# m10motor.net
KiCad netlist of a schematic drawn in Altium Designer
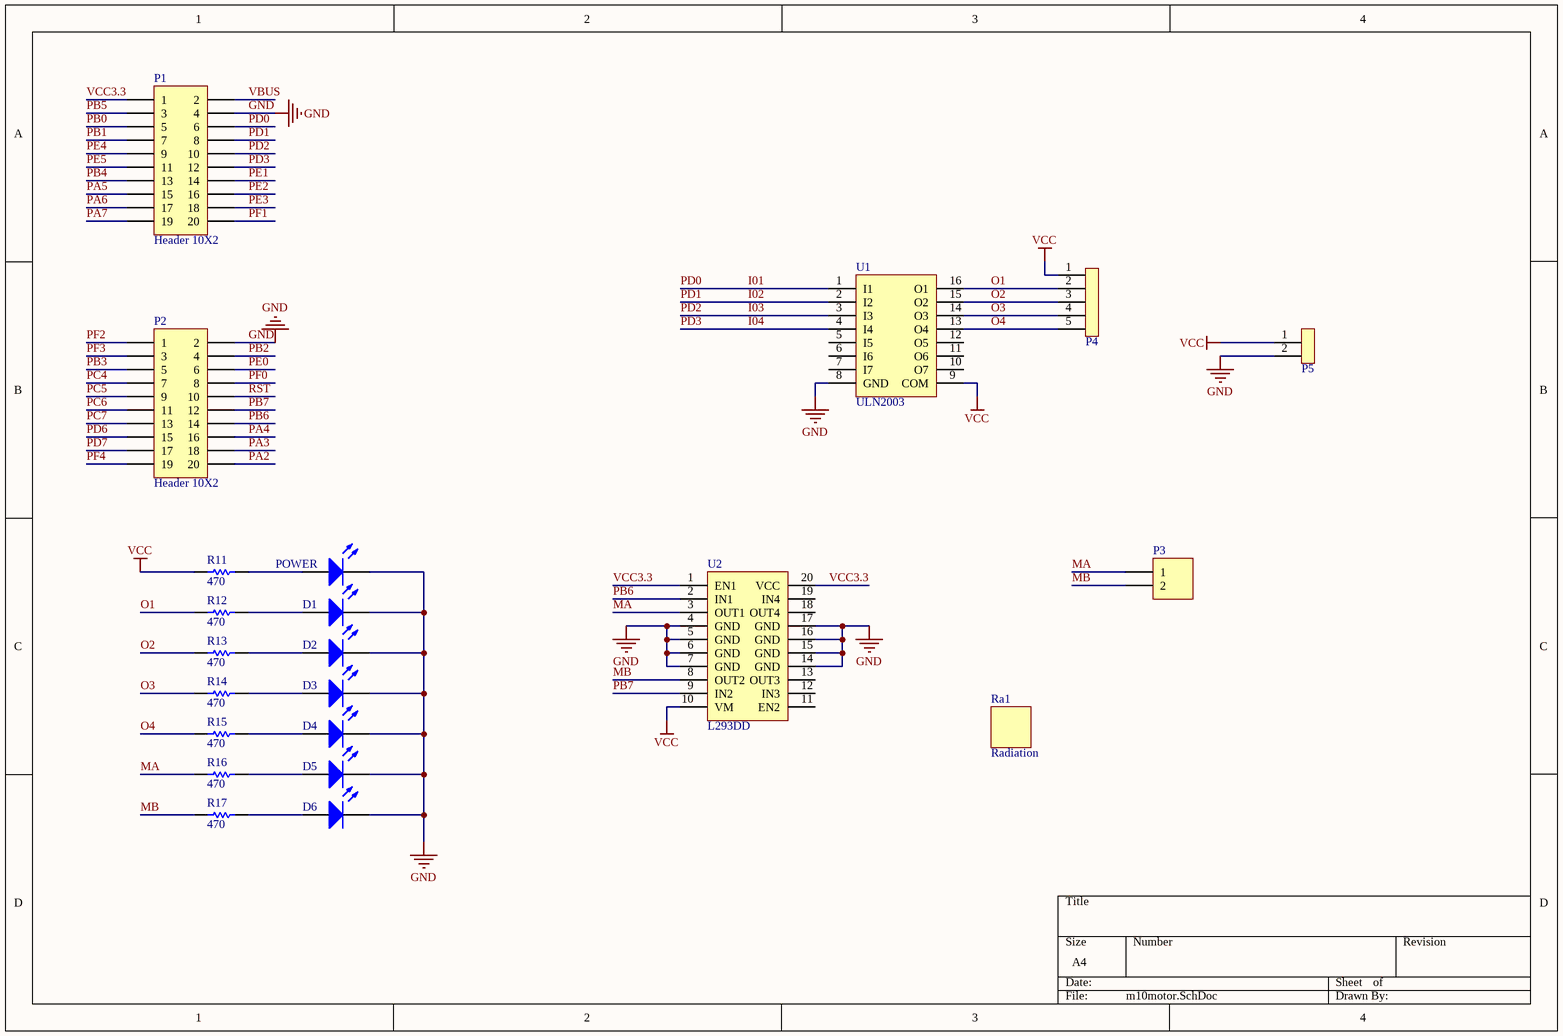
[diagram p0: m10motor.SchDoc]

(export (version "E")
  (design (tool "Eeschema 10.0.6"))
  (components
    (comp (ref "D1")
      (value "LED2")
      (footprint "LED_0603_RED")
      (description "Typical RED, GREEN, YELLOW, AMBER GaAs LED")
      (fields (field (name "PUBLISHER") "Altium Limited"))
      (libsource (lib "Miscellaneous Devices") (part "LED2"))
    )
    (comp (ref "D2")
      (value "LED2")
      (footprint "LED_0603_RED")
      (description "Typical RED, GREEN, YELLOW, AMBER GaAs LED")
      (fields (field (name "PUBLISHER") "Altium Limited"))
      (libsource (lib "Miscellaneous Devices") (part "LED2"))
    )
    (comp (ref "D3")
      (value "LED2")
      (footprint "LED_0603_RED")
      (description "Typical RED, GREEN, YELLOW, AMBER GaAs LED")
      (fields (field (name "PUBLISHER") "Altium Limited"))
      (libsource (lib "Miscellaneous Devices") (part "LED2"))
    )
    (comp (ref "D4")
      (value "LED2")
      (footprint "LED_0603_RED")
      (description "Typical RED, GREEN, YELLOW, AMBER GaAs LED")
      (fields (field (name "PUBLISHER") "Altium Limited"))
      (libsource (lib "Miscellaneous Devices") (part "LED2"))
    )
    (comp (ref "D5")
      (value "LED2")
      (footprint "LED_0603_RED")
      (description "Typical RED, GREEN, YELLOW, AMBER GaAs LED")
      (fields (field (name "PUBLISHER") "Altium Limited"))
      (libsource (lib "Miscellaneous Devices") (part "LED2"))
    )
    (comp (ref "D6")
      (value "LED2")
      (footprint "LED_0603_RED")
      (description "Typical RED, GREEN, YELLOW, AMBER GaAs LED")
      (fields (field (name "PUBLISHER") "Altium Limited"))
      (libsource (lib "Miscellaneous Devices") (part "LED2"))
    )
    (comp (ref "P1")
      (value "Header 10X2")
      (footprint "HDR2X10")
      (description "Header, 10-Pin, Dual row")
      (fields (field (name "PUBLISHER") "Altium Limited"))
      (libsource (lib "Miscellaneous Connectors") (part "Header 10X2"))
    )
    (comp (ref "P2")
      (value "Header 10X2")
      (footprint "HDR2X10")
      (description "Header, 10-Pin, Dual row")
      (fields (field (name "PUBLISHER") "Altium Limited"))
      (libsource (lib "Miscellaneous Connectors") (part "Header 10X2"))
    )
    (comp (ref "P3")
      (value "Header 2")
      (footprint "MKDSN_2RMI")
      (description "Header, 2-Pin")
      (fields (field (name "PUBLISHER") "Altium Limited"))
      (libsource (lib "Miscellaneous Connectors") (part "Header 2"))
    )
    (comp (ref "P4") (value "Header5") (footprint "XHP5") (libsource (lib "m13") (part "Header5")))
    (comp (ref "P5") (value "Header2") (footprint "MKDSN_2RMI") (libsource (lib "m13") (part "Header2")))
    (comp (ref "POWER")
      (value "LED2")
      (footprint "LED_0603_RED")
      (description "Typical RED, GREEN, YELLOW, AMBER GaAs LED")
      (fields (field (name "PUBLISHER") "Altium Limited"))
      (libsource (lib "Miscellaneous Devices") (part "LED2"))
    )
    (comp (ref "R11")
      (value "470")
      (footprint "RES_0603")
      (description "Semiconductor Resistor")
      (fields (field (name "Comment") "Res Semi") (field (name "PUBLISHER") "Altium Limited"))
      (libsource (lib "Miscellaneous Devices") (part "Res Semi"))
    )
    (comp (ref "R12")
      (value "470")
      (footprint "RES_0603")
      (description "Semiconductor Resistor")
      (fields (field (name "Comment") "Res Semi") (field (name "PUBLISHER") "Altium Limited"))
      (libsource (lib "Miscellaneous Devices") (part "Res Semi"))
    )
    (comp (ref "R13")
      (value "470")
      (footprint "RES_0603")
      (description "Semiconductor Resistor")
      (fields (field (name "Comment") "Res Semi") (field (name "PUBLISHER") "Altium Limited"))
      (libsource (lib "Miscellaneous Devices") (part "Res Semi"))
    )
    (comp (ref "R14")
      (value "470")
      (footprint "RES_0603")
      (description "Semiconductor Resistor")
      (fields (field (name "Comment") "Res Semi") (field (name "PUBLISHER") "Altium Limited"))
      (libsource (lib "Miscellaneous Devices") (part "Res Semi"))
    )
    (comp (ref "R15")
      (value "470")
      (footprint "RES_0603")
      (description "Semiconductor Resistor")
      (fields (field (name "Comment") "Res Semi") (field (name "PUBLISHER") "Altium Limited"))
      (libsource (lib "Miscellaneous Devices") (part "Res Semi"))
    )
    (comp (ref "R16")
      (value "470")
      (footprint "RES_0603")
      (description "Semiconductor Resistor")
      (fields (field (name "Comment") "Res Semi") (field (name "PUBLISHER") "Altium Limited"))
      (libsource (lib "Miscellaneous Devices") (part "Res Semi"))
    )
    (comp (ref "R17")
      (value "470")
      (footprint "RES_0603")
      (description "Semiconductor Resistor")
      (fields (field (name "Comment") "Res Semi") (field (name "PUBLISHER") "Altium Limited"))
      (libsource (lib "Miscellaneous Devices") (part "Res Semi"))
    )
    (comp (ref "Ra1") (value "Radiation") (footprint "Radiation") (libsource (lib "m13") (part "Radiation")))
    (comp (ref "U1")
      (value "ULN2003")
      (footprint "PCB_IC:ULN2003A")
      (libsource (lib "SCH_IC") (part "ULN2003"))
    )
    (comp (ref "U2")
      (value "L293DD")
      (footprint "SOP20")
      (description "L293DD MOTOR")
      (libsource (lib "m13") (part "L293DD"))
    )
  )
  (nets
    (net (code "1") (name "/I01") (class "Default")
      (node (ref "P1") (pin "6") (pinfunction "6_6") (pintype "passive"))
      (node (ref "U1") (pin "1") (pinfunction "I1_1") (pintype "passive"))
    )
    (net (code "2") (name "/I02") (class "Default")
      (node (ref "P1") (pin "8") (pinfunction "8_8") (pintype "passive"))
      (node (ref "U1") (pin "2") (pinfunction "I2_2") (pintype "passive"))
    )
    (net (code "3") (name "/I03") (class "Default")
      (node (ref "P1") (pin "10") (pinfunction "10_10") (pintype "passive"))
      (node (ref "U1") (pin "3") (pinfunction "I3_3") (pintype "passive"))
    )
    (net (code "4") (name "/I04") (class "Default")
      (node (ref "P1") (pin "12") (pinfunction "12_12") (pintype "passive"))
      (node (ref "U1") (pin "4") (pinfunction "I4_4") (pintype "passive"))
    )
    (net (code "5") (name "/MA") (class "Default")
      (node (ref "P3") (pin "1") (pinfunction "1_1") (pintype "passive"))
      (node (ref "R16") (pin "1") (pinfunction "1_1") (pintype "passive"))
      (node (ref "U2") (pin "3") (pinfunction "OUT1_3") (pintype "passive"))
    )
    (net (code "6") (name "/MB") (class "Default")
      (node (ref "P3") (pin "2") (pinfunction "2_2") (pintype "passive"))
      (node (ref "R17") (pin "1") (pinfunction "1_1") (pintype "passive"))
      (node (ref "U2") (pin "8") (pinfunction "OUT2_8") (pintype "passive"))
    )
    (net (code "7") (name "/O1") (class "Default")
      (node (ref "P4") (pin "2") (pinfunction "2_2") (pintype "passive"))
      (node (ref "R12") (pin "1") (pinfunction "1_1") (pintype "passive"))
      (node (ref "U1") (pin "16") (pinfunction "O1_16") (pintype "passive"))
    )
    (net (code "8") (name "/O2") (class "Default")
      (node (ref "P4") (pin "3") (pinfunction "3_3") (pintype "passive"))
      (node (ref "R13") (pin "1") (pinfunction "1_1") (pintype "passive"))
      (node (ref "U1") (pin "15") (pinfunction "O2_15") (pintype "passive"))
    )
    (net (code "9") (name "/O3") (class "Default")
      (node (ref "P4") (pin "4") (pinfunction "4_4") (pintype "passive"))
      (node (ref "R14") (pin "1") (pinfunction "1_1") (pintype "passive"))
      (node (ref "U1") (pin "14") (pinfunction "O3_14") (pintype "passive"))
    )
    (net (code "10") (name "/O4") (class "Default")
      (node (ref "P4") (pin "5") (pinfunction "5_5") (pintype "passive"))
      (node (ref "R15") (pin "1") (pinfunction "1_1") (pintype "passive"))
      (node (ref "U1") (pin "13") (pinfunction "O4_13") (pintype "passive"))
    )
    (net (code "11") (name "/PA2") (class "Default")
      (node (ref "P2") (pin "20") (pinfunction "20_20") (pintype "passive"))
    )
    (net (code "12") (name "/PA3") (class "Default")
      (node (ref "P2") (pin "18") (pinfunction "18_18") (pintype "passive"))
    )
    (net (code "13") (name "/PA4") (class "Default")
      (node (ref "P2") (pin "16") (pinfunction "16_16") (pintype "passive"))
    )
    (net (code "14") (name "/PA5") (class "Default")
      (node (ref "P1") (pin "15") (pinfunction "15_15") (pintype "passive"))
    )
    (net (code "15") (name "/PA6") (class "Default")
      (node (ref "P1") (pin "17") (pinfunction "17_17") (pintype "passive"))
    )
    (net (code "16") (name "/PA7") (class "Default")
      (node (ref "P1") (pin "19") (pinfunction "19_19") (pintype "passive"))
    )
    (net (code "17") (name "/PB0") (class "Default")
      (node (ref "P1") (pin "5") (pinfunction "5_5") (pintype "passive"))
    )
    (net (code "18") (name "/PB1") (class "Default")
      (node (ref "P1") (pin "7") (pinfunction "7_7") (pintype "passive"))
    )
    (net (code "19") (name "/PB2") (class "Default")
      (node (ref "P2") (pin "4") (pinfunction "4_4") (pintype "passive"))
    )
    (net (code "20") (name "/PB3") (class "Default")
      (node (ref "P2") (pin "5") (pinfunction "5_5") (pintype "passive"))
    )
    (net (code "21") (name "/PB4") (class "Default")
      (node (ref "P1") (pin "13") (pinfunction "13_13") (pintype "passive"))
    )
    (net (code "22") (name "/PB5") (class "Default")
      (node (ref "P1") (pin "3") (pinfunction "3_3") (pintype "passive"))
    )
    (net (code "23") (name "/PB6") (class "Default")
      (node (ref "P2") (pin "14") (pinfunction "14_14") (pintype "passive"))
      (node (ref "U2") (pin "2") (pinfunction "IN1_2") (pintype "passive"))
    )
    (net (code "24") (name "/PB7") (class "Default")
      (node (ref "P2") (pin "12") (pinfunction "12_12") (pintype "passive"))
      (node (ref "U2") (pin "9") (pinfunction "IN2_9") (pintype "passive"))
    )
    (net (code "25") (name "/PC4") (class "Default")
      (node (ref "P2") (pin "7") (pinfunction "7_7") (pintype "passive"))
    )
    (net (code "26") (name "/PC5") (class "Default")
      (node (ref "P2") (pin "9") (pinfunction "9_9") (pintype "passive"))
    )
    (net (code "27") (name "/PC6") (class "Default")
      (node (ref "P2") (pin "11") (pinfunction "11_11") (pintype "passive"))
    )
    (net (code "28") (name "/PC7") (class "Default")
      (node (ref "P2") (pin "13") (pinfunction "13_13") (pintype "passive"))
    )
    (net (code "29") (name "/PD6") (class "Default")
      (node (ref "P2") (pin "15") (pinfunction "15_15") (pintype "passive"))
    )
    (net (code "30") (name "/PD7") (class "Default")
      (node (ref "P2") (pin "17") (pinfunction "17_17") (pintype "passive"))
    )
    (net (code "31") (name "/PE0") (class "Default")
      (node (ref "P2") (pin "6") (pinfunction "6_6") (pintype "passive"))
    )
    (net (code "32") (name "/PE1") (class "Default")
      (node (ref "P1") (pin "14") (pinfunction "14_14") (pintype "passive"))
    )
    (net (code "33") (name "/PE2") (class "Default")
      (node (ref "P1") (pin "16") (pinfunction "16_16") (pintype "passive"))
    )
    (net (code "34") (name "/PE3") (class "Default")
      (node (ref "P1") (pin "18") (pinfunction "18_18") (pintype "passive"))
    )
    (net (code "35") (name "/PE4") (class "Default")
      (node (ref "P1") (pin "9") (pinfunction "9_9") (pintype "passive"))
    )
    (net (code "36") (name "/PE5") (class "Default")
      (node (ref "P1") (pin "11") (pinfunction "11_11") (pintype "passive"))
    )
    (net (code "37") (name "/PF0") (class "Default")
      (node (ref "P2") (pin "8") (pinfunction "8_8") (pintype "passive"))
    )
    (net (code "38") (name "/PF1") (class "Default")
      (node (ref "P1") (pin "20") (pinfunction "20_20") (pintype "passive"))
    )
    (net (code "39") (name "/PF2") (class "Default")
      (node (ref "P2") (pin "1") (pinfunction "1_1") (pintype "passive"))
    )
    (net (code "40") (name "/PF3") (class "Default")
      (node (ref "P2") (pin "3") (pinfunction "3_3") (pintype "passive"))
    )
    (net (code "41") (name "/PF4") (class "Default")
      (node (ref "P2") (pin "19") (pinfunction "19_19") (pintype "passive"))
    )
    (net (code "42") (name "/RST") (class "Default")
      (node (ref "P2") (pin "10") (pinfunction "10_10") (pintype "passive"))
    )
    (net (code "43") (name "/VBUS") (class "Default")
      (node (ref "P1") (pin "2") (pinfunction "2_2") (pintype "passive"))
    )
    (net (code "44") (name "/VCC3.3") (class "Default")
      (node (ref "P1") (pin "1") (pinfunction "1_1") (pintype "passive"))
      (node (ref "U2") (pin "1") (pinfunction "EN1_1") (pintype "passive"))
      (node (ref "U2") (pin "20") (pinfunction "VCC_20") (pintype "passive"))
    )
    (net (code "45") (name "GND") (class "Default")
      (node (ref "D1") (pin "2") (pinfunction "K_2") (pintype "passive"))
      (node (ref "D2") (pin "2") (pinfunction "K_2") (pintype "passive"))
      (node (ref "D3") (pin "2") (pinfunction "K_2") (pintype "passive"))
      (node (ref "D4") (pin "2") (pinfunction "K_2") (pintype "passive"))
      (node (ref "D5") (pin "2") (pinfunction "K_2") (pintype "passive"))
      (node (ref "D6") (pin "2") (pinfunction "K_2") (pintype "passive"))
      (node (ref "P1") (pin "4") (pinfunction "4_4") (pintype "passive"))
      (node (ref "P2") (pin "2") (pinfunction "2_2") (pintype "passive"))
      (node (ref "P5") (pin "2") (pinfunction "2_2") (pintype "passive"))
      (node (ref "POWER") (pin "2") (pinfunction "K_2") (pintype "passive"))
      (node (ref "U1") (pin "8") (pinfunction "GND_8") (pintype "passive"))
      (node (ref "U2") (pin "14") (pinfunction "GND_14") (pintype "passive"))
      (node (ref "U2") (pin "15") (pinfunction "GND_15") (pintype "passive"))
      (node (ref "U2") (pin "16") (pinfunction "GND_16") (pintype "passive"))
      (node (ref "U2") (pin "17") (pinfunction "GND_17") (pintype "passive"))
      (node (ref "U2") (pin "4") (pinfunction "GND_4") (pintype "passive"))
      (node (ref "U2") (pin "5") (pinfunction "GND_5") (pintype "passive"))
      (node (ref "U2") (pin "6") (pinfunction "GND_6") (pintype "passive"))
      (node (ref "U2") (pin "7") (pinfunction "GND_7") (pintype "passive"))
    )
    (net (code "46") (name "Net-(D1-A)") (class "Default")
      (node (ref "D1") (pin "1") (pinfunction "A_1") (pintype "passive"))
      (node (ref "R12") (pin "2") (pinfunction "2_2") (pintype "passive"))
    )
    (net (code "47") (name "Net-(D2-A)") (class "Default")
      (node (ref "D2") (pin "1") (pinfunction "A_1") (pintype "passive"))
      (node (ref "R13") (pin "2") (pinfunction "2_2") (pintype "passive"))
    )
    (net (code "48") (name "Net-(D3-A)") (class "Default")
      (node (ref "D3") (pin "1") (pinfunction "A_1") (pintype "passive"))
      (node (ref "R14") (pin "2") (pinfunction "2_2") (pintype "passive"))
    )
    (net (code "49") (name "Net-(D4-A)") (class "Default")
      (node (ref "D4") (pin "1") (pinfunction "A_1") (pintype "passive"))
      (node (ref "R15") (pin "2") (pinfunction "2_2") (pintype "passive"))
    )
    (net (code "50") (name "Net-(D5-A)") (class "Default")
      (node (ref "D5") (pin "1") (pinfunction "A_1") (pintype "passive"))
      (node (ref "R16") (pin "2") (pinfunction "2_2") (pintype "passive"))
    )
    (net (code "51") (name "Net-(D6-A)") (class "Default")
      (node (ref "D6") (pin "1") (pinfunction "A_1") (pintype "passive"))
      (node (ref "R17") (pin "2") (pinfunction "2_2") (pintype "passive"))
    )
    (net (code "52") (name "Net-(POWER-A)") (class "Default")
      (node (ref "POWER") (pin "1") (pinfunction "A_1") (pintype "passive"))
      (node (ref "R11") (pin "2") (pinfunction "2_2") (pintype "passive"))
    )
    (net (code "53") (name "VCC") (class "Default")
      (node (ref "P4") (pin "1") (pinfunction "1_1") (pintype "passive"))
      (node (ref "P5") (pin "1") (pinfunction "1_1") (pintype "passive"))
      (node (ref "R11") (pin "1") (pinfunction "1_1") (pintype "passive"))
      (node (ref "U1") (pin "9") (pinfunction "COM_9") (pintype "passive"))
      (node (ref "U2") (pin "10") (pinfunction "VM_10") (pintype "passive"))
    )
    (net (code "54") (name "unconnected-(U1-I5-Pad5)") (class "Default")
      (node (ref "U1") (pin "5") (pinfunction "I5_5") (pintype "passive"))
    )
    (net (code "55") (name "unconnected-(U1-I6-Pad6)") (class "Default")
      (node (ref "U1") (pin "6") (pinfunction "I6_6") (pintype "passive"))
    )
    (net (code "56") (name "unconnected-(U1-I7-Pad7)") (class "Default")
      (node (ref "U1") (pin "7") (pinfunction "I7_7") (pintype "passive"))
    )
    (net (code "57") (name "unconnected-(U1-O5-Pad12)") (class "Default")
      (node (ref "U1") (pin "12") (pinfunction "O5_12") (pintype "passive"))
    )
    (net (code "58") (name "unconnected-(U1-O6-Pad11)") (class "Default")
      (node (ref "U1") (pin "11") (pinfunction "O6_11") (pintype "passive"))
    )
    (net (code "59") (name "unconnected-(U1-O7-Pad10)") (class "Default")
      (node (ref "U1") (pin "10") (pinfunction "O7_10") (pintype "passive"))
    )
    (net (code "60") (name "unconnected-(U2-EN2-Pad11)") (class "Default")
      (node (ref "U2") (pin "11") (pinfunction "EN2_11") (pintype "passive"))
    )
    (net (code "61") (name "unconnected-(U2-IN3-Pad12)") (class "Default")
      (node (ref "U2") (pin "12") (pinfunction "IN3_12") (pintype "passive"))
    )
    (net (code "62") (name "unconnected-(U2-IN4-Pad19)") (class "Default")
      (node (ref "U2") (pin "19") (pinfunction "IN4_19") (pintype "passive"))
    )
    (net (code "63") (name "unconnected-(U2-OUT3-Pad13)") (class "Default")
      (node (ref "U2") (pin "13") (pinfunction "OUT3_13") (pintype "passive"))
    )
    (net (code "64") (name "unconnected-(U2-OUT4-Pad18)") (class "Default")
      (node (ref "U2") (pin "18") (pinfunction "OUT4_18") (pintype "passive"))
    )
  )
)
